# TrenElectricEsquema.net
KiCad netlist of a schematic drawn in EasyEDA
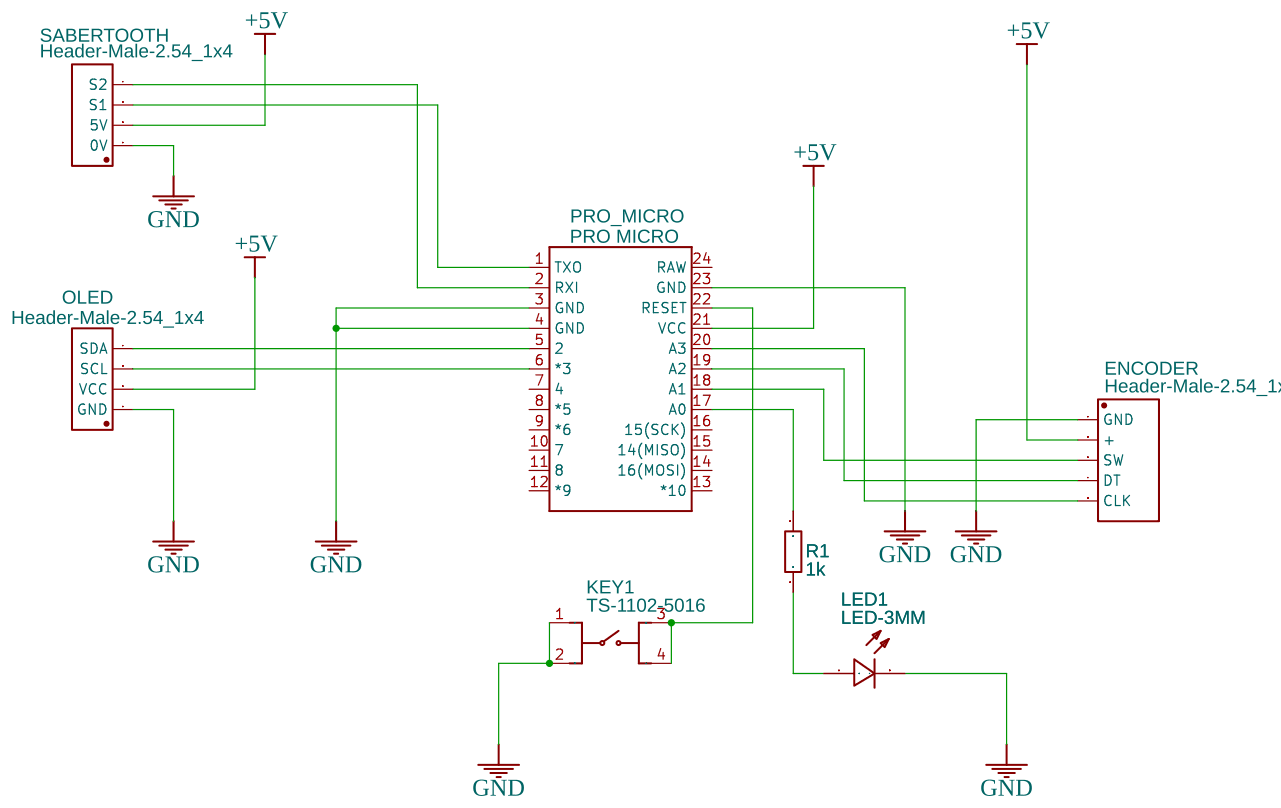
[diagram p0: schematic sheet]

(export (version "E")
  (design (tool "Eeschema 10.0.6"))
  (components
    (comp (ref "ENCODER")
      (value "Header-Male-2.54_1x5")
      (fields
        (field (name "BOM_Manufacturer Part") "210S-1*5P L=11.6MMGold-plated black")
        (field (name "BOM_Supplier Part") "C124379")
      )
      (libsource (lib "") (part "Unknown_805_385"))
    )
    (comp (ref "KEY1")
      (value "TS-1102-5016")
      (fields (field (name "BOM_Supplier Part") "C111609"))
      (libsource (lib "") (part "Unknown_555_475"))
    )
    (comp (ref "LED1")
      (value "LED-3MM")
      (fields
        (field (name "BOM_Manufacturer Part") "204-10SURD/S530-A3")
        (field (name "BOM_Supplier Part") "C99772")
      )
      (libsource (lib "") (part "Unknown_680_490"))
    )
    (comp (ref "OLED")
      (value "Header-Male-2.54_1x4")
      (fields
        (field (name "BOM_Manufacturer Part") "210S-1*4P L=11.6MMGold-plated black")
        (field (name "BOM_Supplier Part") "C124378")
      )
      (libsource (lib "") (part "Unknown_305_345"))
    )
    (comp (ref "PRO_MICRO")
      (value "PRO MICRO")
      (fields (field (name "BOM_Manufacturer Part") "?"))
      (libsource (lib "") (part "Unknown_560_345"))
    )
    (comp (ref "R1")
      (value "1k")
      (fields (field (name "BOM_Manufacturer Part") "?"))
      (libsource (lib "") (part "Res_AXIAL-0.3(1/8W)_EU"))
    )
    (comp (ref "SABERTOOTH")
      (value "Header-Male-2.54_1x4")
      (fields
        (field (name "BOM_Manufacturer Part") "210S-1*4P L=11.6MMGold-plated black")
        (field (name "BOM_Supplier Part") "C124378")
      )
      (libsource (lib "") (part "Unknown_305_215"))
    )
  )
  (nets
    (net (code "1") (name "+5V") (class "Default")
      (node (ref "ENCODER") (pin "2") (pinfunction "+_2") (pintype "unspecified"))
      (node (ref "OLED") (pin "2") (pinfunction "VCC_2") (pintype "unspecified"))
      (node (ref "PRO_MICRO") (pin "21") (pinfunction "VCC_21") (pintype "unspecified"))
      (node (ref "SABERTOOTH") (pin "2") (pinfunction "5V_2") (pintype "unspecified"))
    )
    (net (code "2") (name "GND") (class "Default")
      (node (ref "ENCODER") (pin "1") (pinfunction "GND_1") (pintype "unspecified"))
      (node (ref "KEY1") (pin "1") (pinfunction "1_1") (pintype "unspecified"))
      (node (ref "KEY1") (pin "2") (pinfunction "2_2") (pintype "unspecified"))
      (node (ref "LED1") (pin "2") (pinfunction "-_2") (pintype "unspecified"))
      (node (ref "OLED") (pin "1") (pinfunction "GND_1") (pintype "unspecified"))
      (node (ref "PRO_MICRO") (pin "23") (pinfunction "GND_23") (pintype "unspecified"))
      (node (ref "PRO_MICRO") (pin "3") (pinfunction "GND_3") (pintype "unspecified"))
      (node (ref "PRO_MICRO") (pin "4") (pinfunction "GND_4") (pintype "unspecified"))
      (node (ref "SABERTOOTH") (pin "1") (pinfunction "0V_1") (pintype "unspecified"))
    )
    (net (code "3") (name "Net-(ENCODER-CLK)") (class "Default")
      (node (ref "ENCODER") (pin "5") (pinfunction "CLK_5") (pintype "unspecified"))
      (node (ref "PRO_MICRO") (pin "20") (pinfunction "A3_20") (pintype "unspecified"))
    )
    (net (code "4") (name "Net-(ENCODER-DT)") (class "Default")
      (node (ref "ENCODER") (pin "4") (pinfunction "DT_4") (pintype "unspecified"))
      (node (ref "PRO_MICRO") (pin "19") (pinfunction "A2_19") (pintype "unspecified"))
    )
    (net (code "5") (name "Net-(ENCODER-SW)") (class "Default")
      (node (ref "ENCODER") (pin "3") (pinfunction "SW_3") (pintype "unspecified"))
      (node (ref "PRO_MICRO") (pin "18") (pinfunction "A1_18") (pintype "unspecified"))
    )
    (net (code "6") (name "Net-(LED1-+)") (class "Default")
      (node (ref "LED1") (pin "1") (pinfunction "+_1") (pintype "unspecified"))
      (node (ref "R1") (pin "1") (pinfunction "1_1") (pintype "unspecified"))
    )
    (net (code "7") (name "Net-(OLED-SCL)") (class "Default")
      (node (ref "OLED") (pin "3") (pinfunction "SCL_3") (pintype "unspecified"))
      (node (ref "PRO_MICRO") (pin "6") (pinfunction "*3_6") (pintype "unspecified"))
    )
    (net (code "8") (name "Net-(OLED-SDA)") (class "Default")
      (node (ref "OLED") (pin "4") (pinfunction "SDA_4") (pintype "unspecified"))
      (node (ref "PRO_MICRO") (pin "5") (pinfunction "2_5") (pintype "unspecified"))
    )
    (net (code "9") (name "Net-(PRO_MICRO-A0)") (class "Default")
      (node (ref "PRO_MICRO") (pin "17") (pinfunction "A0_17") (pintype "unspecified"))
      (node (ref "R1") (pin "2") (pinfunction "2_2") (pintype "unspecified"))
    )
    (net (code "10") (name "Net-(PRO_MICRO-RESET)") (class "Default")
      (node (ref "KEY1") (pin "3") (pinfunction "3_3") (pintype "unspecified"))
      (node (ref "KEY1") (pin "4") (pinfunction "4_4") (pintype "unspecified"))
      (node (ref "PRO_MICRO") (pin "22") (pinfunction "RESET_22") (pintype "unspecified"))
    )
    (net (code "11") (name "Net-(PRO_MICRO-RXI)") (class "Default")
      (node (ref "PRO_MICRO") (pin "2") (pinfunction "RXI_2") (pintype "unspecified"))
      (node (ref "SABERTOOTH") (pin "4") (pinfunction "S2_4") (pintype "unspecified"))
    )
    (net (code "12") (name "Net-(PRO_MICRO-TXO)") (class "Default")
      (node (ref "PRO_MICRO") (pin "1") (pinfunction "TXO_1") (pintype "unspecified"))
      (node (ref "SABERTOOTH") (pin "3") (pinfunction "S1_3") (pintype "unspecified"))
    )
    (net (code "13") (name "unconnected-(PRO_MICRO-*5-Pad8)") (class "Default")
      (node (ref "PRO_MICRO") (pin "8") (pinfunction "*5_8") (pintype "unspecified"))
    )
    (net (code "14") (name "unconnected-(PRO_MICRO-*6-Pad9)") (class "Default")
      (node (ref "PRO_MICRO") (pin "9") (pinfunction "*6_9") (pintype "unspecified"))
    )
    (net (code "15") (name "unconnected-(PRO_MICRO-*9-Pad12)") (class "Default")
      (node (ref "PRO_MICRO") (pin "12") (pinfunction "*9_12") (pintype "unspecified"))
    )
    (net (code "16") (name "unconnected-(PRO_MICRO-*10-Pad13)") (class "Default")
      (node (ref "PRO_MICRO") (pin "13") (pinfunction "*10_13") (pintype "unspecified"))
    )
    (net (code "17") (name "unconnected-(PRO_MICRO-4-Pad7)") (class "Default")
      (node (ref "PRO_MICRO") (pin "7") (pinfunction "4_7") (pintype "unspecified"))
    )
    (net (code "18") (name "unconnected-(PRO_MICRO-7-Pad10)") (class "Default")
      (node (ref "PRO_MICRO") (pin "10") (pinfunction "7_10") (pintype "unspecified"))
    )
    (net (code "19") (name "unconnected-(PRO_MICRO-8-Pad11)") (class "Default")
      (node (ref "PRO_MICRO") (pin "11") (pinfunction "8_11") (pintype "unspecified"))
    )
    (net (code "20") (name "unconnected-(PRO_MICRO-14(MISO)-Pad15)") (class "Default")
      (node (ref "PRO_MICRO") (pin "15") (pinfunction "14(MISO)_15") (pintype "unspecified"))
    )
    (net (code "21") (name "unconnected-(PRO_MICRO-15(SCK)-Pad16)") (class "Default")
      (node (ref "PRO_MICRO") (pin "16") (pinfunction "15(SCK)_16") (pintype "unspecified"))
    )
    (net (code "22") (name "unconnected-(PRO_MICRO-16(MOSI)-Pad14)") (class "Default")
      (node (ref "PRO_MICRO") (pin "14") (pinfunction "16(MOSI)_14") (pintype "unspecified"))
    )
    (net (code "23") (name "unconnected-(PRO_MICRO-RAW-Pad24)") (class "Default")
      (node (ref "PRO_MICRO") (pin "24") (pinfunction "RAW_24") (pintype "unspecified"))
    )
  )
)
